# buoys_sch.net
KiCad netlist of a schematic drawn in Altium Designer
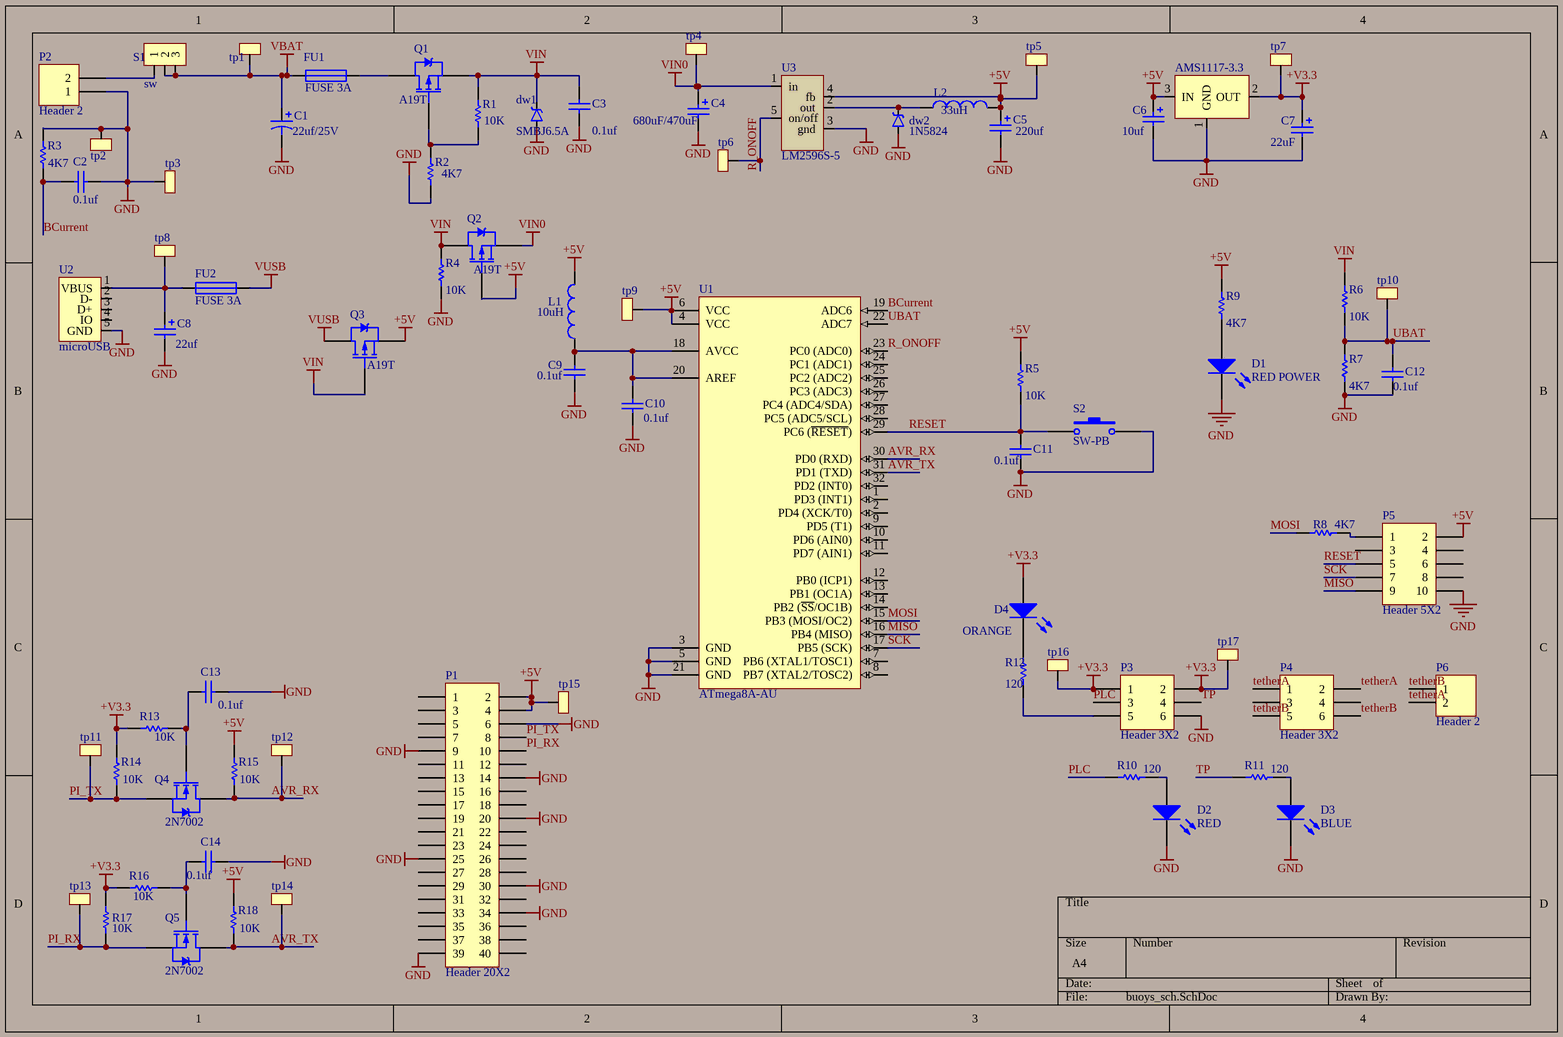
[diagram p0: buoys_sch.SchDoc]

(export (version "E")
  (design (tool "Eeschema 10.0.6"))
  (components
    (comp (ref "AMS1117-3.3")
      (value "Component_3")
      (footprint "SOT223_M")
      (libsource (lib "buoys_sch_lib") (part "Component_3"))
    )
    (comp (ref "C1")
      (value "22uf/25V")
      (footprint "5x5 C")
      (description "Polarized Capacitor (Radial)")
      (fields (field (name "Comment") "Cap Pol1") (field (name "PUBLISHER") "Altium Limited"))
      (libsource (lib "Miscellaneous Devices") (part "Cap Pol1"))
    )
    (comp (ref "C2")
      (value "0.1uf")
      (footprint "6-0805_M")
      (description "Capacitor")
      (fields (field (name "Comment") "Cap") (field (name "PUBLISHER") "Altium Limited"))
      (libsource (lib "Miscellaneous Devices") (part "Cap"))
    )
    (comp (ref "C3")
      (value "0.1uf")
      (footprint "6-0805_M")
      (description "Capacitor")
      (fields (field (name "Comment") "Cap") (field (name "PUBLISHER") "Altium Limited"))
      (libsource (lib "Miscellaneous Devices") (part "Cap"))
    )
    (comp (ref "C4")
      (value "680uF/470uF")
      (footprint "13x13 C")
      (description "Polarized Capacitor (Axial)")
      (fields (field (name "Comment") "Cap Pol2") (field (name "PUBLISHER") "Altium Limited"))
      (libsource (lib "Miscellaneous Devices") (part "Cap Pol2"))
    )
    (comp (ref "C5")
      (value "220uf")
      (footprint "8x8 C")
      (description "Polarized Capacitor (Axial)")
      (fields (field (name "Comment") "Cap Pol2") (field (name "PUBLISHER") "Altium Limited"))
      (libsource (lib "Miscellaneous Devices") (part "Cap Pol2"))
    )
    (comp (ref "C6")
      (value "10uf")
      (footprint "1206")
      (description "Polarized Capacitor (Axial)")
      (fields (field (name "Comment") "Cap Pol2") (field (name "PUBLISHER") "Altium Limited"))
      (libsource (lib "Miscellaneous Devices") (part "Cap Pol2"))
    )
    (comp (ref "C7")
      (value "22uF")
      (footprint "0603")
      (description "Polarized Capacitor (Axial)")
      (fields (field (name "Comment") "Cap Pol2") (field (name "PUBLISHER") "Altium Limited"))
      (libsource (lib "Miscellaneous Devices") (part "Cap Pol2"))
    )
    (comp (ref "C8")
      (value "22uf")
      (footprint "0603")
      (description "Polarized Capacitor (Axial)")
      (fields (field (name "Comment") "Cap Pol2") (field (name "PUBLISHER") "Altium Limited"))
      (libsource (lib "Miscellaneous Devices") (part "Cap Pol2"))
    )
    (comp (ref "C9")
      (value "0.1uf")
      (footprint "6-0805_M")
      (description "Capacitor")
      (fields (field (name "Comment") "Cap") (field (name "PUBLISHER") "Altium Limited"))
      (libsource (lib "Miscellaneous Devices") (part "Cap"))
    )
    (comp (ref "C10")
      (value "0.1uf")
      (footprint "6-0805_M")
      (description "Capacitor")
      (fields (field (name "Comment") "Cap") (field (name "PUBLISHER") "Altium Limited"))
      (libsource (lib "Miscellaneous Devices") (part "Cap"))
    )
    (comp (ref "C11")
      (value "0.1uf")
      (footprint "6-0805_M")
      (description "Capacitor")
      (fields (field (name "Comment") "Cap") (field (name "PUBLISHER") "Altium Limited"))
      (libsource (lib "Miscellaneous Devices") (part "Cap"))
    )
    (comp (ref "C12")
      (value "0.1uf")
      (footprint "6-0805_M")
      (description "Capacitor")
      (fields (field (name "Comment") "Cap") (field (name "PUBLISHER") "Altium Limited"))
      (libsource (lib "Miscellaneous Devices") (part "Cap"))
    )
    (comp (ref "C13")
      (value "0.1uf")
      (footprint "6-0805_M")
      (description "Capacitor")
      (fields (field (name "Comment") "Cap") (field (name "PUBLISHER") "Altium Limited"))
      (libsource (lib "Miscellaneous Devices") (part "Cap"))
    )
    (comp (ref "C14")
      (value "0.1uf")
      (footprint "6-0805_M")
      (description "Capacitor")
      (fields (field (name "Comment") "Cap") (field (name "PUBLISHER") "Altium Limited"))
      (libsource (lib "Miscellaneous Devices") (part "Cap"))
    )
    (comp (ref "D1")
      (value "RED POWER")
      (footprint "6-0805_M")
      (description "Typical RED, GREEN, YELLOW, AMBER GaAs LED")
      (fields (field (name "PUBLISHER") "Altium Limited"))
      (libsource (lib "Miscellaneous Devices") (part "LED2"))
    )
    (comp (ref "D2")
      (value "RED")
      (footprint "6-0805_M")
      (description "Typical RED, GREEN, YELLOW, AMBER GaAs LED")
      (fields (field (name "PUBLISHER") "Altium Limited"))
      (libsource (lib "Miscellaneous Devices") (part "LED2"))
    )
    (comp (ref "D3")
      (value "BLUE")
      (footprint "6-0805_M")
      (description "Typical RED, GREEN, YELLOW, AMBER GaAs LED")
      (fields (field (name "PUBLISHER") "Altium Limited"))
      (libsource (lib "Miscellaneous Devices") (part "LED2"))
    )
    (comp (ref "D4")
      (value "ORANGE")
      (footprint "6-0805_M")
      (description "Typical RED, GREEN, YELLOW, AMBER GaAs LED")
      (fields (field (name "PUBLISHER") "Altium Limited"))
      (libsource (lib "Miscellaneous Devices") (part "LED2"))
    )
    (comp (ref "dw1") (value "SMBJ6.5A") (footprint "SMBJ6.5A") (libsource (lib "常用2") (part "DW")))
    (comp (ref "dw2") (value "1N5824") (footprint "1N5824") (libsource (lib "常用2") (part "DW")))
    (comp (ref "FU1") (value "FUSE 3A") (footprint "1206") (libsource (lib "常用元件库") (part "FUSE")))
    (comp (ref "FU2") (value "FUSE 3A") (footprint "1206") (libsource (lib "常用元件库") (part "FUSE")))
    (comp (ref "L1")
      (value "10uH")
      (footprint "6-0805_M")
      (description "Inductor")
      (fields (field (name "PUBLISHER") "Altium Limited"))
      (libsource (lib "Miscellaneous Devices") (part "Inductor"))
    )
    (comp (ref "L2")
      (value "33uH")
      (footprint "12x12 L")
      (description "Inductor")
      (fields (field (name "PUBLISHER") "Altium Limited"))
      (libsource (lib "Miscellaneous Devices") (part "Inductor"))
    )
    (comp (ref "P1")
      (value "Header 20X2")
      (footprint "HDR2X20")
      (description "Header, 20-Pin, Dual row")
      (fields (field (name "PUBLISHER") "Altium Limited"))
      (libsource (lib "Miscellaneous Connectors") (part "Header 20X2"))
    )
    (comp (ref "P2")
      (value "Header 2")
      (footprint "HDR1X2")
      (description "Header, 2-Pin")
      (fields (field (name "PUBLISHER") "Altium Limited"))
      (libsource (lib "Miscellaneous Connectors") (part "Header 2"))
    )
    (comp (ref "P3")
      (value "Header 3X2")
      (footprint "HDR2X3")
      (description "Header, 3-Pin, Dual row")
      (fields (field (name "PUBLISHER") "Altium Limited"))
      (libsource (lib "Miscellaneous Connectors") (part "Header 3X2"))
    )
    (comp (ref "P4")
      (value "Header 3X2")
      (footprint "HDR2X3")
      (description "Header, 3-Pin, Dual row")
      (fields (field (name "PUBLISHER") "Altium Limited"))
      (libsource (lib "Miscellaneous Connectors") (part "Header 3X2"))
    )
    (comp (ref "P5")
      (value "Header 5X2")
      (footprint "HDR2X5")
      (description "Header, 5-Pin, Dual row")
      (fields (field (name "PUBLISHER") "Altium Limited"))
      (libsource (lib "Miscellaneous Connectors") (part "Header 5X2"))
    )
    (comp (ref "P6")
      (value "Header 2")
      (footprint "tether")
      (description "Header, 2-Pin")
      (fields (field (name "PUBLISHER") "Altium Limited"))
      (libsource (lib "") (part "Header 2_1"))
    )
    (comp (ref "Q1")
      (value "A19T")
      (footprint "A19T")
      (description "P-Channel Power MOSFET")
      (fields (field (name "PUBLISHER") "Altium Limited"))
      (libsource (lib "Miscellaneous Devices") (part "PMOS-2"))
    )
    (comp (ref "Q2")
      (value "A19T")
      (footprint "A19T")
      (description "P-Channel Power MOSFET")
      (fields (field (name "PUBLISHER") "Altium Limited"))
      (libsource (lib "Miscellaneous Devices") (part "PMOS-2"))
    )
    (comp (ref "Q3")
      (value "A19T")
      (footprint "A19T")
      (description "P-Channel Power MOSFET")
      (fields (field (name "PUBLISHER") "Altium Limited"))
      (libsource (lib "Miscellaneous Devices") (part "PMOS-2"))
    )
    (comp (ref "Q4")
      (value "2N7002")
      (footprint "2N7002")
      (description "N-Channel Power MOSFET")
      (fields (field (name "PUBLISHER") "Altium Limited"))
      (libsource (lib "Miscellaneous Devices") (part "NMOS-2"))
    )
    (comp (ref "Q5")
      (value "2N7002")
      (footprint "2N7002")
      (description "N-Channel Power MOSFET")
      (fields (field (name "PUBLISHER") "Altium Limited"))
      (libsource (lib "Miscellaneous Devices") (part "NMOS-2"))
    )
    (comp (ref "R1")
      (value "10K")
      (footprint "6-0805_M")
      (description "Resistor")
      (fields (field (name "Comment") "Res1") (field (name "PUBLISHER") "Altium Limited"))
      (libsource (lib "Miscellaneous Devices") (part "Res1"))
    )
    (comp (ref "R2")
      (value "4K7")
      (footprint "6-0805_M")
      (description "Resistor")
      (fields (field (name "Comment") "Res1") (field (name "PUBLISHER") "Altium Limited"))
      (libsource (lib "Miscellaneous Devices") (part "Res1"))
    )
    (comp (ref "R3")
      (value "4K7")
      (footprint "6-0805_M")
      (description "Resistor")
      (fields (field (name "Comment") "Res1") (field (name "PUBLISHER") "Altium Limited"))
      (libsource (lib "Miscellaneous Devices") (part "Res1"))
    )
    (comp (ref "R4")
      (value "10K")
      (footprint "6-0805_M")
      (description "Resistor")
      (fields (field (name "Comment") "Res1") (field (name "PUBLISHER") "Altium Limited"))
      (libsource (lib "Miscellaneous Devices") (part "Res1"))
    )
    (comp (ref "R5")
      (value "10K")
      (footprint "6-0805_M")
      (description "Resistor")
      (fields (field (name "Comment") "Res1") (field (name "PUBLISHER") "Altium Limited"))
      (libsource (lib "Miscellaneous Devices") (part "Res1"))
    )
    (comp (ref "R6")
      (value "10K")
      (footprint "6-0805_M")
      (description "Resistor")
      (fields (field (name "Comment") "Res1") (field (name "PUBLISHER") "Altium Limited"))
      (libsource (lib "Miscellaneous Devices") (part "Res1"))
    )
    (comp (ref "R7")
      (value "4K7")
      (footprint "6-0805_M")
      (description "Resistor")
      (fields (field (name "Comment") "Res1") (field (name "PUBLISHER") "Altium Limited"))
      (libsource (lib "Miscellaneous Devices") (part "Res1"))
    )
    (comp (ref "R8")
      (value "4K7")
      (footprint "6-0805_M")
      (description "Resistor")
      (fields (field (name "Comment") "Res1") (field (name "PUBLISHER") "Altium Limited"))
      (libsource (lib "Miscellaneous Devices") (part "Res1"))
    )
    (comp (ref "R9")
      (value "4K7")
      (footprint "6-0805_M")
      (description "Resistor")
      (fields (field (name "Comment") "Res1") (field (name "PUBLISHER") "Altium Limited"))
      (libsource (lib "Miscellaneous Devices") (part "Res1"))
    )
    (comp (ref "R10")
      (value "120")
      (footprint "6-0805_M")
      (description "Resistor")
      (fields (field (name "Comment") "Res1") (field (name "PUBLISHER") "Altium Limited"))
      (libsource (lib "Miscellaneous Devices") (part "Res1"))
    )
    (comp (ref "R11")
      (value "120")
      (footprint "6-0805_M")
      (description "Resistor")
      (fields (field (name "Comment") "Res1") (field (name "PUBLISHER") "Altium Limited"))
      (libsource (lib "Miscellaneous Devices") (part "Res1"))
    )
    (comp (ref "R12")
      (value "120")
      (footprint "6-0805_M")
      (description "Resistor")
      (fields (field (name "Comment") "Res1") (field (name "PUBLISHER") "Altium Limited"))
      (libsource (lib "Miscellaneous Devices") (part "Res1"))
    )
    (comp (ref "R13")
      (value "10K")
      (footprint "6-0805_M")
      (description "Resistor")
      (fields (field (name "Comment") "Res1") (field (name "PUBLISHER") "Altium Limited"))
      (libsource (lib "Miscellaneous Devices") (part "Res1"))
    )
    (comp (ref "R14")
      (value "10K")
      (footprint "6-0805_M")
      (description "Resistor")
      (fields (field (name "Comment") "Res1") (field (name "PUBLISHER") "Altium Limited"))
      (libsource (lib "Miscellaneous Devices") (part "Res1"))
    )
    (comp (ref "R15")
      (value "10K")
      (footprint "6-0805_M")
      (description "Resistor")
      (fields (field (name "Comment") "Res1") (field (name "PUBLISHER") "Altium Limited"))
      (libsource (lib "Miscellaneous Devices") (part "Res1"))
    )
    (comp (ref "R16")
      (value "10K")
      (footprint "6-0805_M")
      (description "Resistor")
      (fields (field (name "Comment") "Res1") (field (name "PUBLISHER") "Altium Limited"))
      (libsource (lib "Miscellaneous Devices") (part "Res1"))
    )
    (comp (ref "R17")
      (value "10K")
      (footprint "6-0805_M")
      (description "Resistor")
      (fields (field (name "Comment") "Res1") (field (name "PUBLISHER") "Altium Limited"))
      (libsource (lib "Miscellaneous Devices") (part "Res1"))
    )
    (comp (ref "R18")
      (value "10K")
      (footprint "6-0805_M")
      (description "Resistor")
      (fields (field (name "Comment") "Res1") (field (name "PUBLISHER") "Altium Limited"))
      (libsource (lib "Miscellaneous Devices") (part "Res1"))
    )
    (comp (ref "S1") (value "sw") (footprint "switch-2") (libsource (lib "buoys_sch_lib") (part "sw")))
    (comp (ref "S2")
      (value "SW-PB")
      (footprint "switch4")
      (description "Switch")
      (fields (field (name "PUBLISHER") "Altium Limited"))
      (libsource (lib "Miscellaneous Devices") (part "SW-PB"))
    )
    (comp (ref "tp1") (value "testpoint") (footprint "tp") (libsource (lib "") (part "testpoint_2")))
    (comp (ref "tp2") (value "testpoint") (footprint "tp") (libsource (lib "") (part "testpoint_3")))
    (comp (ref "tp3")
      (value "testpoint")
      (footprint "tp")
      (libsource (lib "buoys_sch_lib") (part "testpoint"))
    )
    (comp (ref "tp4") (value "testpoint") (footprint "tp") (libsource (lib "") (part "testpoint_2")))
    (comp (ref "tp5") (value "testpoint") (footprint "tp") (libsource (lib "") (part "testpoint_2")))
    (comp (ref "tp6") (value "testpoint") (footprint "tp") (libsource (lib "") (part "testpoint_1")))
    (comp (ref "tp7") (value "testpoint") (footprint "tp") (libsource (lib "") (part "testpoint_2")))
    (comp (ref "tp8") (value "testpoint") (footprint "tp") (libsource (lib "") (part "testpoint_2")))
    (comp (ref "tp9") (value "testpoint") (footprint "tp") (libsource (lib "") (part "testpoint_1")))
    (comp (ref "tp10") (value "testpoint") (footprint "tp") (libsource (lib "") (part "testpoint_2")))
    (comp (ref "tp11") (value "testpoint") (footprint "tp") (libsource (lib "") (part "testpoint_2")))
    (comp (ref "tp12") (value "testpoint") (footprint "tp") (libsource (lib "") (part "testpoint_2")))
    (comp (ref "tp13") (value "testpoint") (footprint "tp") (libsource (lib "") (part "testpoint_2")))
    (comp (ref "tp14") (value "testpoint") (footprint "tp") (libsource (lib "") (part "testpoint_2")))
    (comp (ref "tp15")
      (value "testpoint")
      (footprint "tp")
      (libsource (lib "buoys_sch_lib") (part "testpoint"))
    )
    (comp (ref "tp16") (value "testpoint") (footprint "tp") (libsource (lib "") (part "testpoint_2")))
    (comp (ref "tp17") (value "testpoint") (footprint "tp") (libsource (lib "") (part "testpoint_2")))
    (comp (ref "U1")
      (value "ATmega8A-AU")
      (footprint "32A_N")
      (libsource (lib "Atmel Microcontroller megaAVR") (part "ATmega8A-AU"))
    )
    (comp (ref "U2")
      (value "microUSB")
      (footprint "microUSB")
      (libsource (lib "buoys_sch_lib") (part "Component_1"))
    )
    (comp (ref "U3")
      (value "LM2596S-5")
      (footprint "LM2596")
      (libsource (lib "buoys_sch_lib") (part "Component_2"))
    )
  )
  (nets
    (net (code "1") (name "+5V") (class "Default")
      (node (ref "AMS1117-3.3") (pin "3") (pinfunction "IN_3") (pintype "passive"))
      (node (ref "C5") (pin "1") (pinfunction "1_1") (pintype "passive"))
      (node (ref "C6") (pin "1") (pinfunction "1_1") (pintype "passive"))
      (node (ref "L1") (pin "2") (pinfunction "2_2") (pintype "passive"))
      (node (ref "L2") (pin "2") (pinfunction "2_2") (pintype "passive"))
      (node (ref "P1") (pin "2") (pinfunction "2_2") (pintype "passive"))
      (node (ref "P1") (pin "4") (pinfunction "4_4") (pintype "passive"))
      (node (ref "P5") (pin "2") (pinfunction "2_2") (pintype "passive"))
      (node (ref "Q2") (pin "1") (pinfunction "G_1") (pintype "passive"))
      (node (ref "Q3") (pin "3") (pinfunction "S_3") (pintype "passive"))
      (node (ref "R15") (pin "2") (pinfunction "2_2") (pintype "passive"))
      (node (ref "R18") (pin "2") (pinfunction "2_2") (pintype "passive"))
      (node (ref "R5") (pin "2") (pinfunction "2_2") (pintype "passive"))
      (node (ref "R9") (pin "2") (pinfunction "2_2") (pintype "passive"))
      (node (ref "U1") (pin "4") (pinfunction "VCC_4") (pintype "power_in"))
      (node (ref "U1") (pin "6") (pinfunction "VCC_6") (pintype "power_in"))
      (node (ref "U3") (pin "4") (pinfunction "fb_4") (pintype "passive"))
      (node (ref "tp15") (pin "1") (pinfunction "TP_1") (pintype "passive"))
      (node (ref "tp5") (pin "1") (pinfunction "TP_1") (pintype "passive"))
      (node (ref "tp9") (pin "1") (pinfunction "TP_1") (pintype "passive"))
    )
    (net (code "2") (name "+V3.3") (class "Default")
      (node (ref "AMS1117-3.3") (pin "2") (pinfunction "OUT_2") (pintype "passive"))
      (node (ref "C7") (pin "1") (pinfunction "1_1") (pintype "passive"))
      (node (ref "D4") (pin "1") (pinfunction "A_1") (pintype "passive"))
      (node (ref "P3") (pin "1") (pinfunction "1_1") (pintype "passive"))
      (node (ref "P3") (pin "2") (pinfunction "2_2") (pintype "passive"))
      (node (ref "R13") (pin "2") (pinfunction "2_2") (pintype "passive"))
      (node (ref "R14") (pin "2") (pinfunction "2_2") (pintype "passive"))
      (node (ref "R16") (pin "2") (pinfunction "2_2") (pintype "passive"))
      (node (ref "R17") (pin "2") (pinfunction "2_2") (pintype "passive"))
      (node (ref "tp16") (pin "1") (pinfunction "TP_1") (pintype "passive"))
      (node (ref "tp17") (pin "1") (pinfunction "TP_1") (pintype "passive"))
      (node (ref "tp7") (pin "1") (pinfunction "TP_1") (pintype "passive"))
    )
    (net (code "3") (name "/AVR_RX") (class "Default")
      (node (ref "Q4") (pin "2") (pinfunction "D_2") (pintype "passive"))
      (node (ref "R15") (pin "1") (pinfunction "1_1") (pintype "passive"))
      (node (ref "U1") (pin "30") (pinfunction "PD0_(RXD)_30") (pintype "bidirectional"))
      (node (ref "tp12") (pin "1") (pinfunction "TP_1") (pintype "passive"))
    )
    (net (code "4") (name "/AVR_TX") (class "Default")
      (node (ref "Q5") (pin "2") (pinfunction "D_2") (pintype "passive"))
      (node (ref "R18") (pin "1") (pinfunction "1_1") (pintype "passive"))
      (node (ref "U1") (pin "31") (pinfunction "PD1_(TXD)_31") (pintype "bidirectional"))
      (node (ref "tp14") (pin "1") (pinfunction "TP_1") (pintype "passive"))
    )
    (net (code "5") (name "/BCurrent") (class "Default")
      (node (ref "C2") (pin "1") (pinfunction "1_1") (pintype "passive"))
      (node (ref "R3") (pin "1") (pinfunction "1_1") (pintype "passive"))
      (node (ref "U1") (pin "19") (pinfunction "ADC6_19") (pintype "input"))
    )
    (net (code "6") (name "/MISO") (class "Default")
      (node (ref "P5") (pin "9") (pinfunction "9_9") (pintype "passive"))
      (node (ref "U1") (pin "16") (pinfunction "PB4_(MISO)_16") (pintype "bidirectional"))
    )
    (net (code "7") (name "/MOSI") (class "Default")
      (node (ref "R8") (pin "2") (pinfunction "2_2") (pintype "passive"))
      (node (ref "U1") (pin "15") (pinfunction "PB3_(MOSI/OC2)_15") (pintype "bidirectional"))
    )
    (net (code "8") (name "/PI_RX") (class "Default")
      (node (ref "P1") (pin "10") (pinfunction "10_10") (pintype "passive"))
      (node (ref "Q5") (pin "3") (pinfunction "S_3") (pintype "passive"))
      (node (ref "R17") (pin "1") (pinfunction "1_1") (pintype "passive"))
      (node (ref "tp13") (pin "1") (pinfunction "TP_1") (pintype "passive"))
    )
    (net (code "9") (name "/PI_TX") (class "Default")
      (node (ref "P1") (pin "8") (pinfunction "8_8") (pintype "passive"))
      (node (ref "Q4") (pin "3") (pinfunction "S_3") (pintype "passive"))
      (node (ref "R14") (pin "1") (pinfunction "1_1") (pintype "passive"))
      (node (ref "tp11") (pin "1") (pinfunction "TP_1") (pintype "passive"))
    )
    (net (code "10") (name "/PLC") (class "Default")
      (node (ref "P3") (pin "3") (pinfunction "3_3") (pintype "passive"))
      (node (ref "R10") (pin "2") (pinfunction "2_2") (pintype "passive"))
    )
    (net (code "11") (name "/RESET") (class "Default")
      (node (ref "C11") (pin "1") (pinfunction "1_1") (pintype "passive"))
      (node (ref "P5") (pin "5") (pinfunction "5_5") (pintype "passive"))
      (node (ref "R5") (pin "1") (pinfunction "1_1") (pintype "passive"))
      (node (ref "S2") (pin "1") (pinfunction "1_1") (pintype "passive"))
      (node (ref "U1") (pin "29") (pinfunction "PC6_(~{RESET})_29") (pintype "bidirectional"))
    )
    (net (code "12") (name "/R_ONOFF") (class "Default")
      (node (ref "U1") (pin "23") (pinfunction "PC0_(ADC0)_23") (pintype "bidirectional"))
      (node (ref "U3") (pin "5") (pinfunction "on/off_5") (pintype "passive"))
      (node (ref "tp6") (pin "1") (pinfunction "TP_1") (pintype "passive"))
    )
    (net (code "13") (name "/SCK") (class "Default")
      (node (ref "P5") (pin "7") (pinfunction "7_7") (pintype "passive"))
      (node (ref "U1") (pin "17") (pinfunction "PB5_(SCK)_17") (pintype "bidirectional"))
    )
    (net (code "14") (name "/TP") (class "Default")
      (node (ref "P3") (pin "4") (pinfunction "4_4") (pintype "passive"))
      (node (ref "R11") (pin "2") (pinfunction "2_2") (pintype "passive"))
    )
    (net (code "15") (name "/UBAT") (class "Default")
      (node (ref "C12") (pin "2") (pinfunction "2_2") (pintype "passive"))
      (node (ref "R6") (pin "1") (pinfunction "1_1") (pintype "passive"))
      (node (ref "R7") (pin "2") (pinfunction "2_2") (pintype "passive"))
      (node (ref "U1") (pin "22") (pinfunction "ADC7_22") (pintype "input"))
      (node (ref "tp10") (pin "1") (pinfunction "TP_1") (pintype "passive"))
    )
    (net (code "16") (name "/tetherA") (class "Default")
      (node (ref "P4") (pin "1") (pinfunction "1_1") (pintype "passive"))
      (node (ref "P4") (pin "2") (pinfunction "2_2") (pintype "passive"))
      (node (ref "P6") (pin "2") (pinfunction "2_2") (pintype "passive"))
    )
    (net (code "17") (name "/tetherB") (class "Default")
      (node (ref "P4") (pin "5") (pinfunction "5_5") (pintype "passive"))
      (node (ref "P4") (pin "6") (pinfunction "6_6") (pintype "passive"))
      (node (ref "P6") (pin "1") (pinfunction "1_1") (pintype "passive"))
    )
    (net (code "18") (name "GND") (class "Default")
      (node (ref "AMS1117-3.3") (pin "1") (pinfunction "GND_1") (pintype "passive"))
      (node (ref "C1") (pin "2") (pinfunction "2_2") (pintype "passive"))
      (node (ref "C10") (pin "2") (pinfunction "2_2") (pintype "passive"))
      (node (ref "C11") (pin "2") (pinfunction "2_2") (pintype "passive"))
      (node (ref "C12") (pin "1") (pinfunction "1_1") (pintype "passive"))
      (node (ref "C13") (pin "1") (pinfunction "1_1") (pintype "passive"))
      (node (ref "C14") (pin "1") (pinfunction "1_1") (pintype "passive"))
      (node (ref "C2") (pin "2") (pinfunction "2_2") (pintype "passive"))
      (node (ref "C3") (pin "2") (pinfunction "2_2") (pintype "passive"))
      (node (ref "C4") (pin "2") (pinfunction "2_2") (pintype "passive"))
      (node (ref "C5") (pin "2") (pinfunction "2_2") (pintype "passive"))
      (node (ref "C6") (pin "2") (pinfunction "2_2") (pintype "passive"))
      (node (ref "C7") (pin "2") (pinfunction "2_2") (pintype "passive"))
      (node (ref "C8") (pin "2") (pinfunction "2_2") (pintype "passive"))
      (node (ref "C9") (pin "1") (pinfunction "1_1") (pintype "passive"))
      (node (ref "D1") (pin "2") (pinfunction "K_2") (pintype "passive"))
      (node (ref "D2") (pin "2") (pinfunction "K_2") (pintype "passive"))
      (node (ref "D3") (pin "2") (pinfunction "K_2") (pintype "passive"))
      (node (ref "P1") (pin "14") (pinfunction "14_14") (pintype "passive"))
      (node (ref "P1") (pin "20") (pinfunction "20_20") (pintype "passive"))
      (node (ref "P1") (pin "25") (pinfunction "25_25") (pintype "passive"))
      (node (ref "P1") (pin "30") (pinfunction "30_30") (pintype "passive"))
      (node (ref "P1") (pin "34") (pinfunction "34_34") (pintype "passive"))
      (node (ref "P1") (pin "39") (pinfunction "39_39") (pintype "passive"))
      (node (ref "P1") (pin "6") (pinfunction "6_6") (pintype "passive"))
      (node (ref "P1") (pin "9") (pinfunction "9_9") (pintype "passive"))
      (node (ref "P2") (pin "1") (pinfunction "1_1") (pintype "passive"))
      (node (ref "P3") (pin "6") (pinfunction "6_6") (pintype "passive"))
      (node (ref "P5") (pin "10") (pinfunction "10_10") (pintype "passive"))
      (node (ref "R2") (pin "1") (pinfunction "1_1") (pintype "passive"))
      (node (ref "R3") (pin "2") (pinfunction "2_2") (pintype "passive"))
      (node (ref "R4") (pin "1") (pinfunction "1_1") (pintype "passive"))
      (node (ref "R7") (pin "1") (pinfunction "1_1") (pintype "passive"))
      (node (ref "S2") (pin "2") (pinfunction "2_2") (pintype "passive"))
      (node (ref "U1") (pin "21") (pinfunction "GND_21") (pintype "power_in"))
      (node (ref "U1") (pin "3") (pinfunction "GND_3") (pintype "power_in"))
      (node (ref "U1") (pin "5") (pinfunction "GND_5") (pintype "power_in"))
      (node (ref "U2") (pin "5") (pinfunction "GND_5") (pintype "power_in"))
      (node (ref "U3") (pin "3") (pinfunction "gnd_3") (pintype "passive"))
      (node (ref "dw1") (pin "A") (pintype "passive"))
      (node (ref "dw2") (pin "A") (pintype "passive"))
      (node (ref "tp2") (pin "1") (pinfunction "TP_1") (pintype "passive"))
      (node (ref "tp3") (pin "1") (pinfunction "TP_1") (pintype "passive"))
    )
    (net (code "19") (name "Net-(D1-A)") (class "Default")
      (node (ref "D1") (pin "1") (pinfunction "A_1") (pintype "passive"))
      (node (ref "R9") (pin "1") (pinfunction "1_1") (pintype "passive"))
    )
    (net (code "20") (name "Net-(D2-A)") (class "Default")
      (node (ref "D2") (pin "1") (pinfunction "A_1") (pintype "passive"))
      (node (ref "R10") (pin "1") (pinfunction "1_1") (pintype "passive"))
    )
    (net (code "21") (name "Net-(D3-A)") (class "Default")
      (node (ref "D3") (pin "1") (pinfunction "A_1") (pintype "passive"))
      (node (ref "R11") (pin "1") (pinfunction "1_1") (pintype "passive"))
    )
    (net (code "22") (name "Net-(D4-K)") (class "Default")
      (node (ref "D4") (pin "2") (pinfunction "K_2") (pintype "passive"))
      (node (ref "R12") (pin "1") (pinfunction "1_1") (pintype "passive"))
    )
    (net (code "23") (name "Net-(P2-Pad2)") (class "Default")
      (node (ref "P2") (pin "2") (pinfunction "2_2") (pintype "passive"))
      (node (ref "S1") (pin "1") (pinfunction "1_1") (pintype "passive"))
    )
    (net (code "24") (name "Net-(P3-Pad5)") (class "Default")
      (node (ref "P3") (pin "5") (pinfunction "5_5") (pintype "passive"))
      (node (ref "R12") (pin "2") (pinfunction "2_2") (pintype "passive"))
    )
    (net (code "25") (name "Net-(P5-Pad1)") (class "Default")
      (node (ref "P5") (pin "1") (pinfunction "1_1") (pintype "passive"))
      (node (ref "R8") (pin "1") (pinfunction "1_1") (pintype "passive"))
    )
    (net (code "26") (name "Net-(Q1-D)") (class "Default")
      (node (ref "FU1") (pin "2") (pinfunction "2_2") (pintype "passive"))
      (node (ref "Q1") (pin "2") (pinfunction "D_2") (pintype "passive"))
    )
    (net (code "27") (name "Net-(Q1-G)") (class "Default")
      (node (ref "Q1") (pin "1") (pinfunction "G_1") (pintype "passive"))
      (node (ref "R1") (pin "2") (pinfunction "2_2") (pintype "passive"))
      (node (ref "R2") (pin "2") (pinfunction "2_2") (pintype "passive"))
    )
    (net (code "28") (name "Net-(Q4-G)") (class "Default")
      (node (ref "C13") (pin "2") (pinfunction "2_2") (pintype "passive"))
      (node (ref "Q4") (pin "1") (pinfunction "G_1") (pintype "passive"))
      (node (ref "R13") (pin "1") (pinfunction "1_1") (pintype "passive"))
    )
    (net (code "29") (name "Net-(Q5-G)") (class "Default")
      (node (ref "C14") (pin "2") (pinfunction "2_2") (pintype "passive"))
      (node (ref "Q5") (pin "1") (pinfunction "G_1") (pintype "passive"))
      (node (ref "R16") (pin "1") (pinfunction "1_1") (pintype "passive"))
    )
    (net (code "30") (name "Net-(U1-AREF)") (class "Default")
      (node (ref "C10") (pin "1") (pinfunction "1_1") (pintype "passive"))
      (node (ref "C9") (pin "2") (pinfunction "2_2") (pintype "passive"))
      (node (ref "L1") (pin "1") (pinfunction "1_1") (pintype "passive"))
      (node (ref "U1") (pin "18") (pinfunction "AVCC_18") (pintype "power_in"))
      (node (ref "U1") (pin "20") (pinfunction "AREF_20") (pintype "power_in"))
    )
    (net (code "31") (name "Net-(U2-VBUS)") (class "Default")
      (node (ref "C8") (pin "1") (pinfunction "1_1") (pintype "passive"))
      (node (ref "FU2") (pin "1") (pinfunction "1_1") (pintype "passive"))
      (node (ref "U2") (pin "1") (pinfunction "VBUS_1") (pintype "power_in"))
      (node (ref "tp8") (pin "1") (pinfunction "TP_1") (pintype "passive"))
    )
    (net (code "32") (name "Net-(U3-out)") (class "Default")
      (node (ref "L2") (pin "1") (pinfunction "1_1") (pintype "passive"))
      (node (ref "U3") (pin "2") (pinfunction "out_2") (pintype "passive"))
      (node (ref "dw2") (pin "K") (pintype "passive"))
    )
    (net (code "33") (name "VBAT") (class "Default")
      (node (ref "C1") (pin "1") (pinfunction "1_1") (pintype "passive"))
      (node (ref "FU1") (pin "1") (pinfunction "1_1") (pintype "passive"))
      (node (ref "S1") (pin "2") (pinfunction "2_2") (pintype "passive"))
      (node (ref "S1") (pin "3") (pinfunction "3_3") (pintype "passive"))
      (node (ref "tp1") (pin "1") (pinfunction "TP_1") (pintype "passive"))
    )
    (net (code "34") (name "VIN") (class "Default")
      (node (ref "C3") (pin "1") (pinfunction "1_1") (pintype "passive"))
      (node (ref "Q1") (pin "3") (pinfunction "S_3") (pintype "passive"))
      (node (ref "Q2") (pin "2") (pinfunction "D_2") (pintype "passive"))
      (node (ref "Q3") (pin "1") (pinfunction "G_1") (pintype "passive"))
      (node (ref "R1") (pin "1") (pinfunction "1_1") (pintype "passive"))
      (node (ref "R4") (pin "2") (pinfunction "2_2") (pintype "passive"))
      (node (ref "R6") (pin "2") (pinfunction "2_2") (pintype "passive"))
      (node (ref "dw1") (pin "K") (pintype "passive"))
    )
    (net (code "35") (name "VIN0") (class "Default")
      (node (ref "C4") (pin "1") (pinfunction "1_1") (pintype "passive"))
      (node (ref "Q2") (pin "3") (pinfunction "S_3") (pintype "passive"))
      (node (ref "U3") (pin "1") (pinfunction "in_1") (pintype "passive"))
      (node (ref "tp4") (pin "1") (pinfunction "TP_1") (pintype "passive"))
    )
    (net (code "36") (name "VUSB") (class "Default")
      (node (ref "FU2") (pin "2") (pinfunction "2_2") (pintype "passive"))
      (node (ref "Q3") (pin "2") (pinfunction "D_2") (pintype "passive"))
    )
    (net (code "37") (name "unconnected-(P1-Pad1)") (class "Default")
      (node (ref "P1") (pin "1") (pinfunction "1_1") (pintype "passive"))
    )
    (net (code "38") (name "unconnected-(P1-Pad3)") (class "Default")
      (node (ref "P1") (pin "3") (pinfunction "3_3") (pintype "passive"))
    )
    (net (code "39") (name "unconnected-(P1-Pad5)") (class "Default")
      (node (ref "P1") (pin "5") (pinfunction "5_5") (pintype "passive"))
    )
    (net (code "40") (name "unconnected-(P1-Pad7)") (class "Default")
      (node (ref "P1") (pin "7") (pinfunction "7_7") (pintype "passive"))
    )
    (net (code "41") (name "unconnected-(P1-Pad11)") (class "Default")
      (node (ref "P1") (pin "11") (pinfunction "11_11") (pintype "passive"))
    )
    (net (code "42") (name "unconnected-(P1-Pad12)") (class "Default")
      (node (ref "P1") (pin "12") (pinfunction "12_12") (pintype "passive"))
    )
    (net (code "43") (name "unconnected-(P1-Pad13)") (class "Default")
      (node (ref "P1") (pin "13") (pinfunction "13_13") (pintype "passive"))
    )
    (net (code "44") (name "unconnected-(P1-Pad15)") (class "Default")
      (node (ref "P1") (pin "15") (pinfunction "15_15") (pintype "passive"))
    )
    (net (code "45") (name "unconnected-(P1-Pad16)") (class "Default")
      (node (ref "P1") (pin "16") (pinfunction "16_16") (pintype "passive"))
    )
    (net (code "46") (name "unconnected-(P1-Pad17)") (class "Default")
      (node (ref "P1") (pin "17") (pinfunction "17_17") (pintype "passive"))
    )
    (net (code "47") (name "unconnected-(P1-Pad18)") (class "Default")
      (node (ref "P1") (pin "18") (pinfunction "18_18") (pintype "passive"))
    )
    (net (code "48") (name "unconnected-(P1-Pad19)") (class "Default")
      (node (ref "P1") (pin "19") (pinfunction "19_19") (pintype "passive"))
    )
    (net (code "49") (name "unconnected-(P1-Pad21)") (class "Default")
      (node (ref "P1") (pin "21") (pinfunction "21_21") (pintype "passive"))
    )
    (net (code "50") (name "unconnected-(P1-Pad22)") (class "Default")
      (node (ref "P1") (pin "22") (pinfunction "22_22") (pintype "passive"))
    )
    (net (code "51") (name "unconnected-(P1-Pad23)") (class "Default")
      (node (ref "P1") (pin "23") (pinfunction "23_23") (pintype "passive"))
    )
    (net (code "52") (name "unconnected-(P1-Pad24)") (class "Default")
      (node (ref "P1") (pin "24") (pinfunction "24_24") (pintype "passive"))
    )
    (net (code "53") (name "unconnected-(P1-Pad26)") (class "Default")
      (node (ref "P1") (pin "26") (pinfunction "26_26") (pintype "passive"))
    )
    (net (code "54") (name "unconnected-(P1-Pad27)") (class "Default")
      (node (ref "P1") (pin "27") (pinfunction "27_27") (pintype "passive"))
    )
    (net (code "55") (name "unconnected-(P1-Pad28)") (class "Default")
      (node (ref "P1") (pin "28") (pinfunction "28_28") (pintype "passive"))
    )
    (net (code "56") (name "unconnected-(P1-Pad29)") (class "Default")
      (node (ref "P1") (pin "29") (pinfunction "29_29") (pintype "passive"))
    )
    (net (code "57") (name "unconnected-(P1-Pad31)") (class "Default")
      (node (ref "P1") (pin "31") (pinfunction "31_31") (pintype "passive"))
    )
    (net (code "58") (name "unconnected-(P1-Pad32)") (class "Default")
      (node (ref "P1") (pin "32") (pinfunction "32_32") (pintype "passive"))
    )
    (net (code "59") (name "unconnected-(P1-Pad33)") (class "Default")
      (node (ref "P1") (pin "33") (pinfunction "33_33") (pintype "passive"))
    )
    (net (code "60") (name "unconnected-(P1-Pad35)") (class "Default")
      (node (ref "P1") (pin "35") (pinfunction "35_35") (pintype "passive"))
    )
    (net (code "61") (name "unconnected-(P1-Pad36)") (class "Default")
      (node (ref "P1") (pin "36") (pinfunction "36_36") (pintype "passive"))
    )
    (net (code "62") (name "unconnected-(P1-Pad37)") (class "Default")
      (node (ref "P1") (pin "37") (pinfunction "37_37") (pintype "passive"))
    )
    (net (code "63") (name "unconnected-(P1-Pad38)") (class "Default")
      (node (ref "P1") (pin "38") (pinfunction "38_38") (pintype "passive"))
    )
    (net (code "64") (name "unconnected-(P1-Pad40)") (class "Default")
      (node (ref "P1") (pin "40") (pinfunction "40_40") (pintype "passive"))
    )
    (net (code "65") (name "unconnected-(P4-Pad3)") (class "Default")
      (node (ref "P4") (pin "3") (pinfunction "3_3") (pintype "passive"))
    )
    (net (code "66") (name "unconnected-(P4-Pad4)") (class "Default")
      (node (ref "P4") (pin "4") (pinfunction "4_4") (pintype "passive"))
    )
    (net (code "67") (name "unconnected-(P5-Pad3)") (class "Default")
      (node (ref "P5") (pin "3") (pinfunction "3_3") (pintype "passive"))
    )
    (net (code "68") (name "unconnected-(P5-Pad4)") (class "Default")
      (node (ref "P5") (pin "4") (pinfunction "4_4") (pintype "passive"))
    )
    (net (code "69") (name "unconnected-(P5-Pad6)") (class "Default")
      (node (ref "P5") (pin "6") (pinfunction "6_6") (pintype "passive"))
    )
    (net (code "70") (name "unconnected-(P5-Pad8)") (class "Default")
      (node (ref "P5") (pin "8") (pinfunction "8_8") (pintype "passive"))
    )
    (net (code "71") (name "unconnected-(U1-PB0_(ICP1)-Pad12)") (class "Default")
      (node (ref "U1") (pin "12") (pinfunction "PB0_(ICP1)_12") (pintype "bidirectional"))
    )
    (net (code "72") (name "unconnected-(U1-PB1_(OC1A)-Pad13)") (class "Default")
      (node (ref "U1") (pin "13") (pinfunction "PB1_(OC1A)_13") (pintype "bidirectional"))
    )
    (net (code "73") (name "unconnected-(U1-PB2_(~{SS}{slash}OC1B)-Pad14)") (class "Default")
      (node (ref "U1") (pin "14") (pinfunction "PB2_(~{SS}/OC1B)_14") (pintype "bidirectional"))
    )
    (net (code "74") (name "unconnected-(U1-PB6_(XTAL1{slash}TOSC1)-Pad7)") (class "Default")
      (node (ref "U1") (pin "7") (pinfunction "PB6_(XTAL1/TOSC1)_7") (pintype "bidirectional"))
    )
    (net (code "75") (name "unconnected-(U1-PB7_(XTAL2{slash}TOSC2)-Pad8)") (class "Default")
      (node (ref "U1") (pin "8") (pinfunction "PB7_(XTAL2/TOSC2)_8") (pintype "bidirectional"))
    )
    (net (code "76") (name "unconnected-(U1-PC1_(ADC1)-Pad24)") (class "Default")
      (node (ref "U1") (pin "24") (pinfunction "PC1_(ADC1)_24") (pintype "bidirectional"))
    )
    (net (code "77") (name "unconnected-(U1-PC2_(ADC2)-Pad25)") (class "Default")
      (node (ref "U1") (pin "25") (pinfunction "PC2_(ADC2)_25") (pintype "bidirectional"))
    )
    (net (code "78") (name "unconnected-(U1-PC3_(ADC3)-Pad26)") (class "Default")
      (node (ref "U1") (pin "26") (pinfunction "PC3_(ADC3)_26") (pintype "bidirectional"))
    )
    (net (code "79") (name "unconnected-(U1-PC4_(ADC4{slash}SDA)-Pad27)") (class "Default")
      (node (ref "U1") (pin "27") (pinfunction "PC4_(ADC4/SDA)_27") (pintype "bidirectional"))
    )
    (net (code "80") (name "unconnected-(U1-PC5_(ADC5{slash}SCL)-Pad28)") (class "Default")
      (node (ref "U1") (pin "28") (pinfunction "PC5_(ADC5/SCL)_28") (pintype "bidirectional"))
    )
    (net (code "81") (name "unconnected-(U1-PD2_(INT0)-Pad32)") (class "Default")
      (node (ref "U1") (pin "32") (pinfunction "PD2_(INT0)_32") (pintype "bidirectional"))
    )
    (net (code "82") (name "unconnected-(U1-PD3_(INT1)-Pad1)") (class "Default")
      (node (ref "U1") (pin "1") (pinfunction "PD3_(INT1)_1") (pintype "bidirectional"))
    )
    (net (code "83") (name "unconnected-(U1-PD4_(XCK{slash}T0)-Pad2)") (class "Default")
      (node (ref "U1") (pin "2") (pinfunction "PD4_(XCK/T0)_2") (pintype "bidirectional"))
    )
    (net (code "84") (name "unconnected-(U1-PD5_(T1)-Pad9)") (class "Default")
      (node (ref "U1") (pin "9") (pinfunction "PD5_(T1)_9") (pintype "bidirectional"))
    )
    (net (code "85") (name "unconnected-(U1-PD6_(AIN0)-Pad10)") (class "Default")
      (node (ref "U1") (pin "10") (pinfunction "PD6_(AIN0)_10") (pintype "bidirectional"))
    )
    (net (code "86") (name "unconnected-(U1-PD7_(AIN1)-Pad11)") (class "Default")
      (node (ref "U1") (pin "11") (pinfunction "PD7_(AIN1)_11") (pintype "bidirectional"))
    )
    (net (code "87") (name "unconnected-(U2-D+-Pad3)") (class "Default")
      (node (ref "U2") (pin "3") (pinfunction "D+_3") (pintype "passive"))
    )
    (net (code "88") (name "unconnected-(U2-D--Pad2)") (class "Default")
      (node (ref "U2") (pin "2") (pinfunction "D-_2") (pintype "passive"))
    )
    (net (code "89") (name "unconnected-(U2-IO-Pad4)") (class "Default")
      (node (ref "U2") (pin "4") (pinfunction "IO_4") (pintype "passive"))
    )
  )
)
